# Display-RTC.net
KiCad netlist of a schematic drawn in Altium Designer
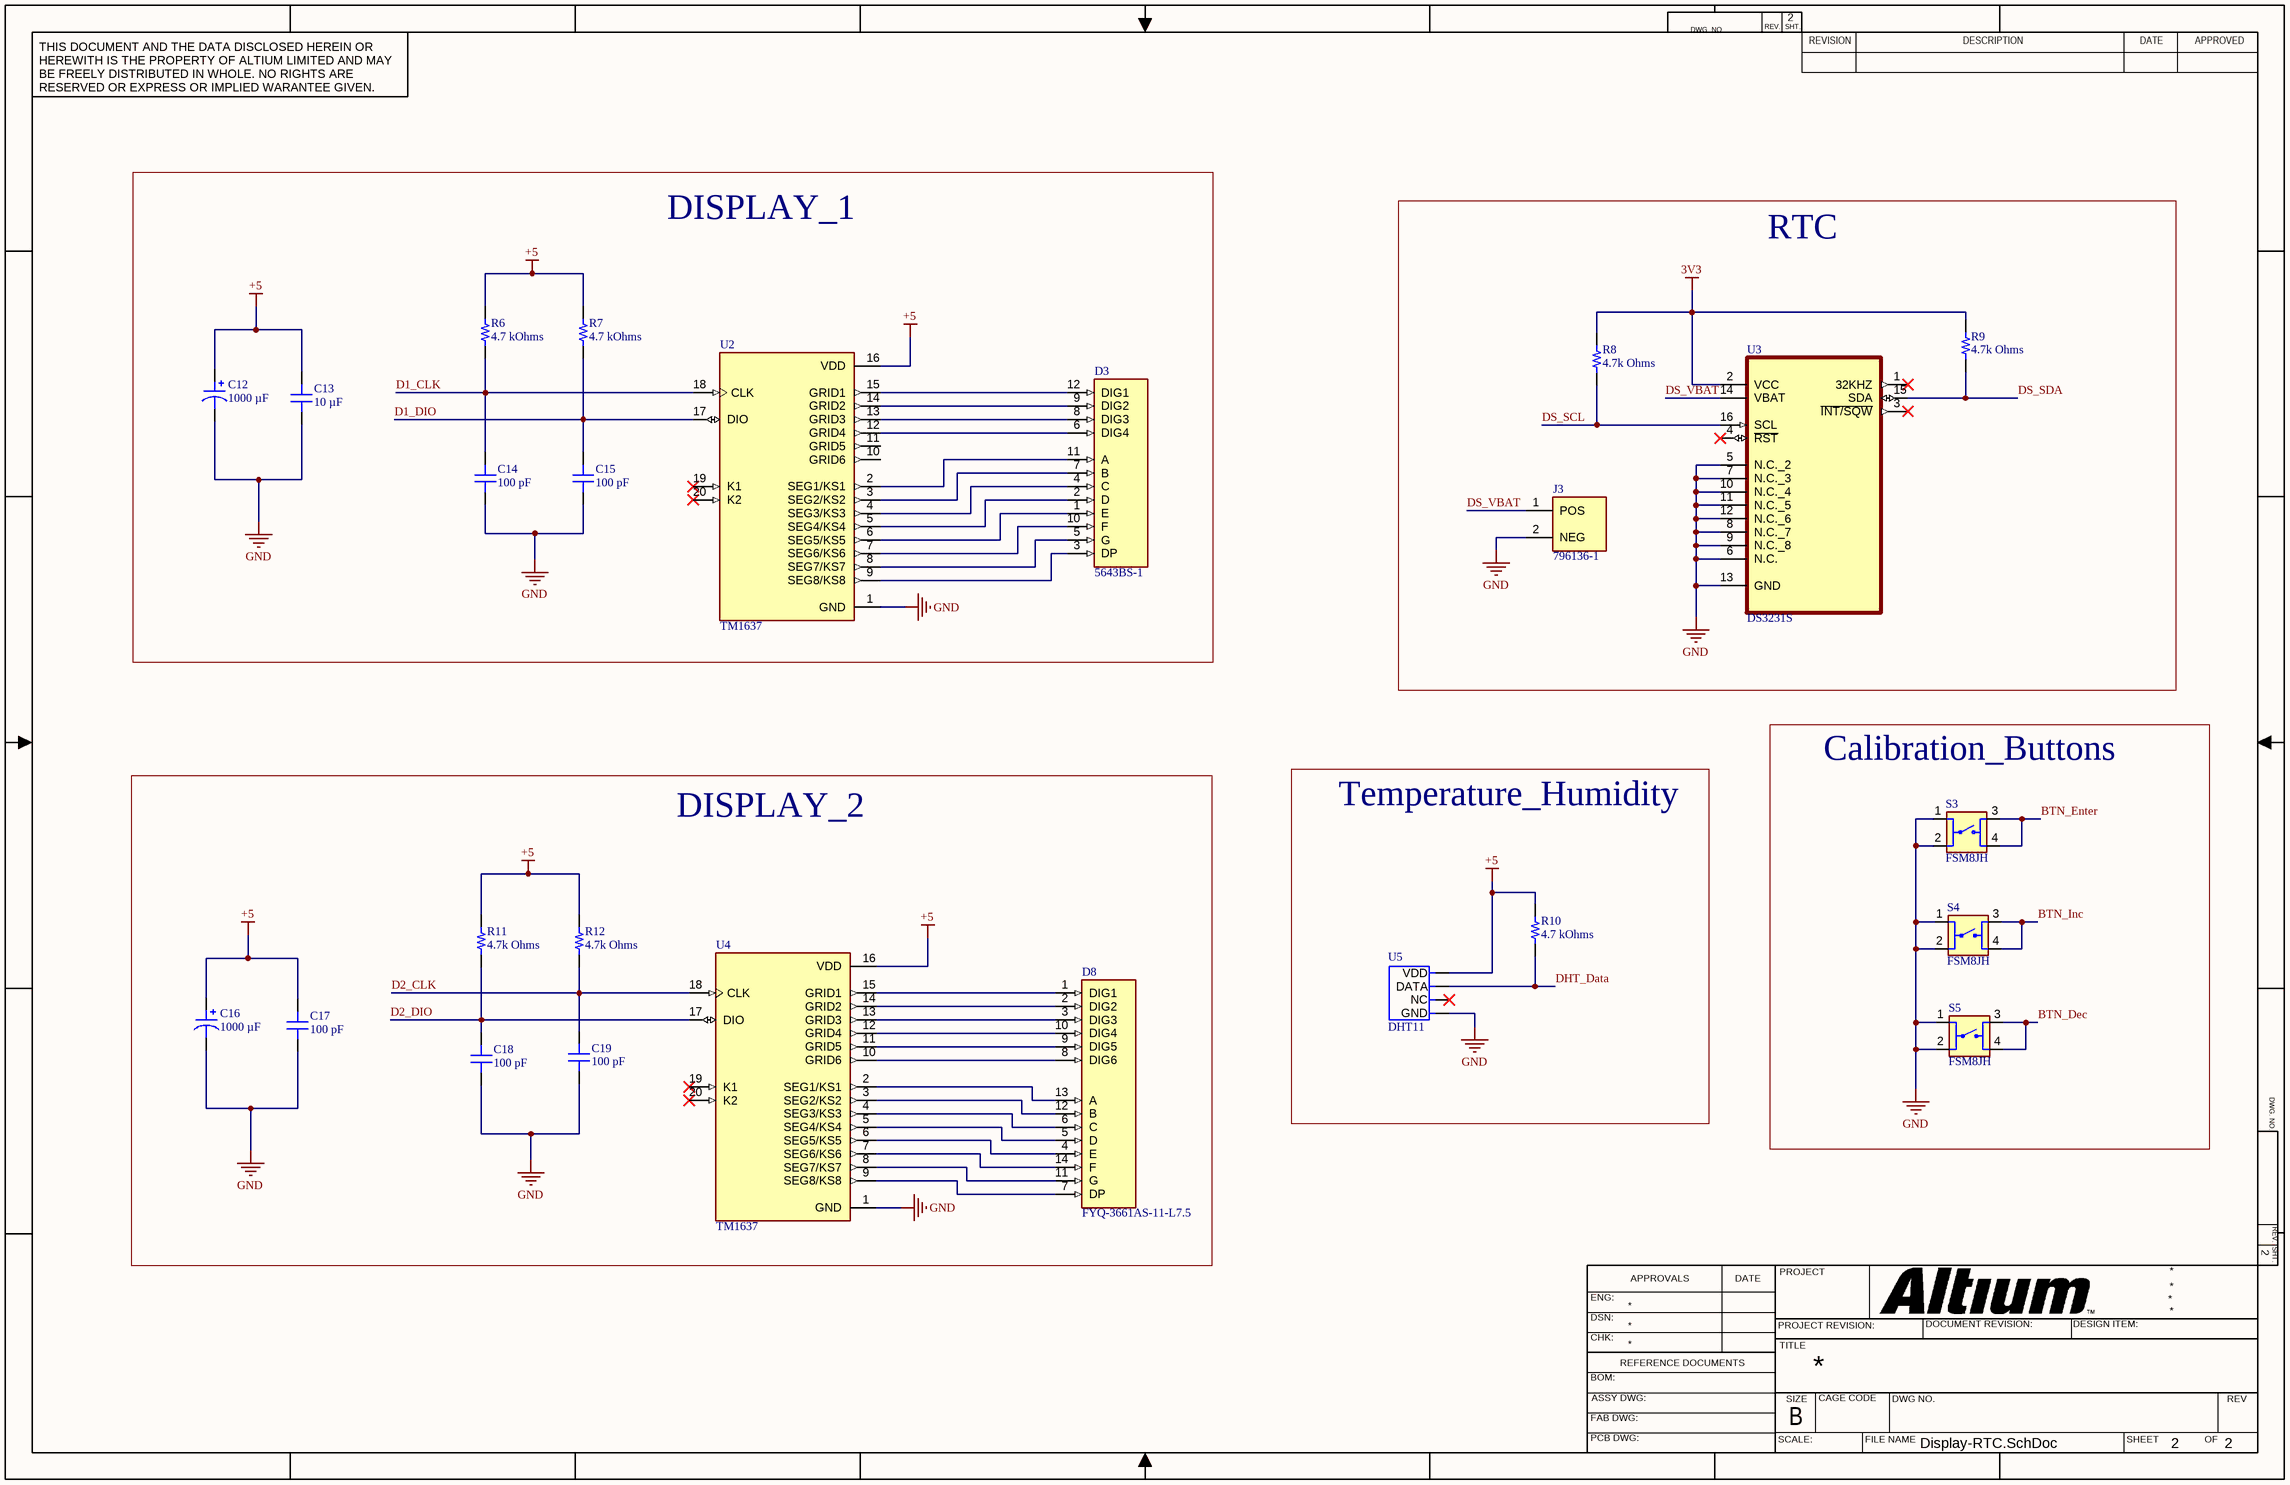
[diagram p0: Display-RTC.SchDoc]

(export (version "E")
  (design (tool "Eeschema 10.0.6"))
  (components
    (comp (ref "C12")
      (value "1000 µF")
      (footprint "CAP AL TH D8 L3.5 H12.5")
      (description "CAP ALUM 1000UF 20% 6.3V RADIAL")
      (fields
        (field (name "PART NUMBER") "ECA-0JHG102")
        (field (name "MANUFACTURER") "Panasonic Electronic Components")
      )
      (libsource (lib "Celestial Altium Library - altium_library") (part "Polarised Capacitor"))
    )
    (comp (ref "C13")
      (value "10 µF")
      (footprint "CAP 0402_1005")
      (description "CAP CER 10UF 10V X5R 0402")
      (fields
        (field (name "PART NUMBER") "CL05A106MP8NUB8")
        (field (name "CAPACITANCE") "10 µF")
        (field (name "MANUFACTURER") "Samsung Electro-Mechanics")
      )
      (libsource (lib "Celestial Altium Library - altium_library") (part "Capacitor"))
    )
    (comp (ref "C14")
      (value "100 pF")
      (footprint "CAP 0402_1005")
      (description "CAP CER 100PF 50V C0G/NP0 0402")
      (fields
        (field (name "PART NUMBER") "500X07N101MV4T")
        (field (name "CAPACITANCE") "100 pF")
        (field (name "MANUFACTURER") "Johanson Dielectrics Inc.")
      )
      (libsource (lib "Celestial Altium Library - altium_library") (part "Capacitor"))
    )
    (comp (ref "C15")
      (value "100 pF")
      (footprint "CAP 0402_1005")
      (description "CAP CER 100PF 50V C0G/NP0 0402")
      (fields
        (field (name "PART NUMBER") "500X07N101MV4T")
        (field (name "CAPACITANCE") "100 pF")
        (field (name "MANUFACTURER") "Johanson Dielectrics Inc.")
      )
      (libsource (lib "Celestial Altium Library - altium_library") (part "Capacitor"))
    )
    (comp (ref "C16")
      (value "1000 µF")
      (footprint "CAP AL TH D8 L3.5 H12.5")
      (description "CAP ALUM 1000UF 20% 6.3V RADIAL")
      (fields
        (field (name "PART NUMBER") "ECA-0JHG102")
        (field (name "MANUFACTURER") "Panasonic Electronic Components")
      )
      (libsource (lib "Celestial Altium Library - altium_library") (part "Polarised Capacitor"))
    )
    (comp (ref "C17")
      (value "100 pF")
      (footprint "CAP 0402_1005")
      (description "CAP CER 100PF 50V C0G/NP0 0402")
      (fields
        (field (name "PART NUMBER") "500X07N101MV4T")
        (field (name "CAPACITANCE") "100 pF")
        (field (name "MANUFACTURER") "Johanson Dielectrics Inc.")
      )
      (libsource (lib "Celestial Altium Library - altium_library") (part "Capacitor"))
    )
    (comp (ref "C18")
      (value "100 pF")
      (footprint "CAP 0402_1005")
      (description "CAP CER 100PF 50V C0G/NP0 0402")
      (fields
        (field (name "PART NUMBER") "500X07N101MV4T")
        (field (name "CAPACITANCE") "100 pF")
        (field (name "MANUFACTURER") "Johanson Dielectrics Inc.")
      )
      (libsource (lib "Celestial Altium Library - altium_library") (part "Capacitor"))
    )
    (comp (ref "C19")
      (value "100 pF")
      (footprint "CAP 0402_1005")
      (description "CAP CER 100PF 50V C0G/NP0 0402")
      (fields
        (field (name "PART NUMBER") "500X07N101MV4T")
        (field (name "CAPACITANCE") "100 pF")
        (field (name "MANUFACTURER") "Johanson Dielectrics Inc.")
      )
      (libsource (lib "Celestial Altium Library - altium_library") (part "Capacitor"))
    )
    (comp (ref "D3") (value "5643BS-1") (footprint "5643BS-1") (libsource (lib "MyAltLib") (part "5643BS-1")))
    (comp (ref "D8")
      (value "FYQ-3661AS-11-L7.5")
      (footprint "FYQ-3661AS-11-L7.5")
      (libsource (lib "MyAltLib") (part "FYQ-3661AS-11-L7.5"))
    )
    (comp (ref "J3")
      (value "796136-1")
      (footprint "TE_796136-1")
      (description "BATTERY HOLDER COIN 20MM SMD")
      (libsource (lib "MyAltLib") (part "796136-1"))
    )
    (comp (ref "R6")
      (value "4.7 kOhms")
      (footprint "RES 0805_2012")
      (description "CRGH0805 1% 4K7 0.33W")
      (fields
        (field (name "PART NUMBER") "CRGH0805F4K7")
        (field (name "MANUFACTURER") "TE Connectivity Passive Product")
      )
      (libsource (lib "Celestial Altium Library - altium_library") (part "Resistor"))
    )
    (comp (ref "R7")
      (value "4.7 kOhms")
      (footprint "RES 0805_2012")
      (description "CRGH0805 1% 4K7 0.33W")
      (fields
        (field (name "PART NUMBER") "CRGH0805F4K7")
        (field (name "MANUFACTURER") "TE Connectivity Passive Product")
      )
      (libsource (lib "Celestial Altium Library - altium_library") (part "Resistor"))
    )
    (comp (ref "R8")
      (value "4.7k Ohms")
      (footprint "RES 0805_2012")
      (description "RES 0 OHM JUMPER 0805")
      (fields
        (field (name "PART NUMBER") "TLRZ2ATTD")
        (field (name "MANUFACTURER") "KOA Speer Electronics, Inc.")
      )
      (libsource (lib "Celestial Altium Library - altium_library") (part "Resistor"))
    )
    (comp (ref "R9")
      (value "4.7k Ohms")
      (footprint "RES 0805_2012")
      (description "RES 0 OHM JUMPER 0805")
      (fields
        (field (name "PART NUMBER") "TLRZ2ATTD")
        (field (name "MANUFACTURER") "KOA Speer Electronics, Inc.")
      )
      (libsource (lib "Celestial Altium Library - altium_library") (part "Resistor"))
    )
    (comp (ref "R10")
      (value "4.7 kOhms")
      (footprint "RES 0805_2012")
      (description "CRGH0805 1% 4K7 0.33W")
      (fields
        (field (name "PART NUMBER") "CRGH0805F4K7")
        (field (name "MANUFACTURER") "TE Connectivity Passive Product")
      )
      (libsource (lib "Celestial Altium Library - altium_library") (part "Resistor"))
    )
    (comp (ref "R11")
      (value "4.7k Ohms")
      (footprint "RES 0805_2012")
      (description "RES 0 OHM JUMPER 0805")
      (fields
        (field (name "PART NUMBER") "TLRZ2ATTD")
        (field (name "MANUFACTURER") "KOA Speer Electronics, Inc.")
      )
      (libsource (lib "Celestial Altium Library - altium_library") (part "Resistor"))
    )
    (comp (ref "R12")
      (value "4.7k Ohms")
      (footprint "RES 0805_2012")
      (description "RES 0 OHM JUMPER 0805")
      (fields
        (field (name "PART NUMBER") "TLRZ2ATTD")
        (field (name "MANUFACTURER") "KOA Speer Electronics, Inc.")
      )
      (libsource (lib "Celestial Altium Library - altium_library") (part "Resistor"))
    )
    (comp (ref "S3")
      (value "FSM8JH")
      (footprint "SW_FSM8JH")
      (description "Tactile Switch SPST-NO Top Actuated Through Hole")
      (fields (field (name "MF") "TE Connectivity"))
      (libsource (lib "MyAltLib") (part "FSM8JH"))
    )
    (comp (ref "S4")
      (value "FSM8JH")
      (footprint "SW_FSM8JH")
      (description "Tactile Switch SPST-NO Top Actuated Through Hole")
      (fields (field (name "MF") "TE Connectivity"))
      (libsource (lib "MyAltLib") (part "FSM8JH"))
    )
    (comp (ref "S5")
      (value "FSM8JH")
      (footprint "SW_FSM8JH")
      (description "Tactile Switch SPST-NO Top Actuated Through Hole")
      (fields (field (name "MF") "TE Connectivity"))
      (libsource (lib "MyAltLib") (part "FSM8JH"))
    )
    (comp (ref "U2")
      (value "TM1637")
      (footprint "TM1637")
      (description "LED Drive Control Special Circuit")
      (fields (field (name "MF") "Titan Micro Electronics"))
      (libsource (lib "MyAltLib") (part "TM1637"))
    )
    (comp (ref "U3")
      (value "DS3231S")
      (footprint "SOIC16")
      (description "Real Time Clock (RTC) IC Clock/Calendar - IÂ²C, 2-Wire Serial 16-SOIC (0.295, 7.50mm Width)")
      (fields (field (name "MF") "Maxim Integrated") (field (name "MP") "DS3231S#"))
      (libsource (lib "MyAltLib") (part "DS3231S"))
    )
    (comp (ref "U4")
      (value "TM1637")
      (footprint "TM1637")
      (description "LED Drive Control Special Circuit")
      (fields (field (name "MF") "Titan Micro Electronics"))
      (libsource (lib "MyAltLib") (part "TM1637"))
    )
    (comp (ref "U5")
      (value "DHT11")
      (footprint "DHT11")
      (description "Servo AC 100 ~ 120VAC Supply 10A 120V Load")
      (fields (field (name "MF") "Panasonic Industrial Automation Sales"))
      (libsource (lib "MyAltLib") (part "DHT11"))
    )
  )
  (nets
    (net (code "1") (name "+5") (class "Default")
      (node (ref "C12") (pin "1") (pinfunction "1_1") (pintype "passive"))
      (node (ref "C13") (pin "2") (pinfunction "2_2") (pintype "passive"))
      (node (ref "C16") (pin "1") (pinfunction "1_1") (pintype "passive"))
      (node (ref "C17") (pin "2") (pinfunction "2_2") (pintype "passive"))
      (node (ref "R10") (pin "2") (pinfunction "2_2") (pintype "passive"))
      (node (ref "R11") (pin "2") (pinfunction "2_2") (pintype "passive"))
      (node (ref "R12") (pin "2") (pinfunction "2_2") (pintype "passive"))
      (node (ref "R6") (pin "2") (pinfunction "2_2") (pintype "passive"))
      (node (ref "R7") (pin "2") (pinfunction "2_2") (pintype "passive"))
      (node (ref "U2") (pin "16") (pinfunction "VDD_16") (pintype "power_in"))
      (node (ref "U4") (pin "16") (pinfunction "VDD_16") (pintype "power_in"))
      (node (ref "U5") (pin "1") (pinfunction "VDD_1") (pintype "power_in"))
    )
    (net (code "2") (name "/BTN_Dec") (class "Default")
      (node (ref "S5") (pin "3") (pinfunction "3_3") (pintype "passive"))
      (node (ref "S5") (pin "4") (pinfunction "4_4") (pintype "passive"))
    )
    (net (code "3") (name "/BTN_Enter") (class "Default")
      (node (ref "S3") (pin "3") (pinfunction "3_3") (pintype "passive"))
      (node (ref "S3") (pin "4") (pinfunction "4_4") (pintype "passive"))
    )
    (net (code "4") (name "/BTN_Inc") (class "Default")
      (node (ref "S4") (pin "3") (pinfunction "3_3") (pintype "passive"))
      (node (ref "S4") (pin "4") (pinfunction "4_4") (pintype "passive"))
    )
    (net (code "5") (name "/D1_CLK") (class "Default")
      (node (ref "C14") (pin "2") (pinfunction "2_2") (pintype "passive"))
      (node (ref "R6") (pin "1") (pinfunction "1_1") (pintype "passive"))
      (node (ref "U2") (pin "18") (pinfunction "CLK_18") (pintype "input"))
    )
    (net (code "6") (name "/D1_DIO") (class "Default")
      (node (ref "C15") (pin "2") (pinfunction "2_2") (pintype "passive"))
      (node (ref "R7") (pin "1") (pinfunction "1_1") (pintype "passive"))
      (node (ref "U2") (pin "17") (pinfunction "DIO_17") (pintype "bidirectional"))
    )
    (net (code "7") (name "/D2_CLK") (class "Default")
      (node (ref "C19") (pin "2") (pinfunction "2_2") (pintype "passive"))
      (node (ref "R12") (pin "1") (pinfunction "1_1") (pintype "passive"))
      (node (ref "U4") (pin "18") (pinfunction "CLK_18") (pintype "input"))
    )
    (net (code "8") (name "/D2_DIO") (class "Default")
      (node (ref "C18") (pin "2") (pinfunction "2_2") (pintype "passive"))
      (node (ref "R11") (pin "1") (pinfunction "1_1") (pintype "passive"))
      (node (ref "U4") (pin "17") (pinfunction "DIO_17") (pintype "bidirectional"))
    )
    (net (code "9") (name "/DHT_Data") (class "Default")
      (node (ref "R10") (pin "1") (pinfunction "1_1") (pintype "passive"))
      (node (ref "U5") (pin "2") (pinfunction "DATA_2") (pintype "bidirectional"))
    )
    (net (code "10") (name "/DS_SCL") (class "Default")
      (node (ref "R8") (pin "1") (pinfunction "1_1") (pintype "passive"))
      (node (ref "U3") (pin "16") (pinfunction "SCL_16") (pintype "input"))
    )
    (net (code "11") (name "/DS_SDA") (class "Default")
      (node (ref "R9") (pin "1") (pinfunction "1_1") (pintype "passive"))
      (node (ref "U3") (pin "15") (pinfunction "SDA_15") (pintype "bidirectional"))
    )
    (net (code "12") (name "/DS_VBAT") (class "Default")
      (node (ref "J3") (pin "1") (pinfunction "POS_1") (pintype "passive"))
      (node (ref "U3") (pin "14") (pinfunction "VBAT_14") (pintype "power_in"))
    )
    (net (code "13") (name "3V3") (class "Default")
      (node (ref "R8") (pin "2") (pinfunction "2_2") (pintype "passive"))
      (node (ref "R9") (pin "2") (pinfunction "2_2") (pintype "passive"))
      (node (ref "U3") (pin "2") (pinfunction "VCC_2") (pintype "power_in"))
    )
    (net (code "14") (name "GND") (class "Default")
      (node (ref "C12") (pin "2") (pinfunction "2_2") (pintype "passive"))
      (node (ref "C13") (pin "1") (pinfunction "1_1") (pintype "passive"))
      (node (ref "C14") (pin "1") (pinfunction "1_1") (pintype "passive"))
      (node (ref "C15") (pin "1") (pinfunction "1_1") (pintype "passive"))
      (node (ref "C16") (pin "2") (pinfunction "2_2") (pintype "passive"))
      (node (ref "C17") (pin "1") (pinfunction "1_1") (pintype "passive"))
      (node (ref "C18") (pin "1") (pinfunction "1_1") (pintype "passive"))
      (node (ref "C19") (pin "1") (pinfunction "1_1") (pintype "passive"))
      (node (ref "J3") (pin "2") (pinfunction "NEG_2") (pintype "passive"))
      (node (ref "S3") (pin "1") (pinfunction "1_1") (pintype "passive"))
      (node (ref "S3") (pin "2") (pinfunction "2_2") (pintype "passive"))
      (node (ref "S4") (pin "1") (pinfunction "1_1") (pintype "passive"))
      (node (ref "S4") (pin "2") (pinfunction "2_2") (pintype "passive"))
      (node (ref "S5") (pin "1") (pinfunction "1_1") (pintype "passive"))
      (node (ref "S5") (pin "2") (pinfunction "2_2") (pintype "passive"))
      (node (ref "U2") (pin "1") (pinfunction "GND_1") (pintype "power_in"))
      (node (ref "U3") (pin "10") (pinfunction "N.C._4_10") (pintype "passive"))
      (node (ref "U3") (pin "11") (pinfunction "N.C._5_11") (pintype "passive"))
      (node (ref "U3") (pin "12") (pinfunction "N.C._6_12") (pintype "passive"))
      (node (ref "U3") (pin "13") (pinfunction "GND_13") (pintype "passive"))
      (node (ref "U3") (pin "5") (pinfunction "N.C._2_5") (pintype "passive"))
      (node (ref "U3") (pin "6") (pinfunction "N.C._6") (pintype "passive"))
      (node (ref "U3") (pin "7") (pinfunction "N.C._3_7") (pintype "passive"))
      (node (ref "U3") (pin "8") (pinfunction "N.C._7_8") (pintype "passive"))
      (node (ref "U3") (pin "9") (pinfunction "N.C._8_9") (pintype "passive"))
      (node (ref "U4") (pin "1") (pinfunction "GND_1") (pintype "power_in"))
      (node (ref "U5") (pin "4") (pinfunction "GND_4") (pintype "power_in"))
    )
    (net (code "15") (name "Net-(D3-A)") (class "Default")
      (node (ref "D3") (pin "11") (pinfunction "A_11") (pintype "input"))
      (node (ref "U2") (pin "2") (pinfunction "SEG1/KS1_2") (pintype "output"))
    )
    (net (code "16") (name "Net-(D3-B)") (class "Default")
      (node (ref "D3") (pin "7") (pinfunction "B_7") (pintype "input"))
      (node (ref "U2") (pin "3") (pinfunction "SEG2/KS2_3") (pintype "output"))
    )
    (net (code "17") (name "Net-(D3-C)") (class "Default")
      (node (ref "D3") (pin "4") (pinfunction "C_4") (pintype "input"))
      (node (ref "U2") (pin "4") (pinfunction "SEG3/KS3_4") (pintype "output"))
    )
    (net (code "18") (name "Net-(D3-D)") (class "Default")
      (node (ref "D3") (pin "2") (pinfunction "D_2") (pintype "input"))
      (node (ref "U2") (pin "5") (pinfunction "SEG4/KS4_5") (pintype "output"))
    )
    (net (code "19") (name "Net-(D3-DIG1)") (class "Default")
      (node (ref "D3") (pin "12") (pinfunction "DIG1_12") (pintype "input"))
      (node (ref "U2") (pin "15") (pinfunction "GRID1_15") (pintype "output"))
    )
    (net (code "20") (name "Net-(D3-DIG2)") (class "Default")
      (node (ref "D3") (pin "9") (pinfunction "DIG2_9") (pintype "input"))
      (node (ref "U2") (pin "14") (pinfunction "GRID2_14") (pintype "output"))
    )
    (net (code "21") (name "Net-(D3-DIG3)") (class "Default")
      (node (ref "D3") (pin "8") (pinfunction "DIG3_8") (pintype "input"))
      (node (ref "U2") (pin "13") (pinfunction "GRID3_13") (pintype "output"))
    )
    (net (code "22") (name "Net-(D3-DIG4)") (class "Default")
      (node (ref "D3") (pin "6") (pinfunction "DIG4_6") (pintype "input"))
      (node (ref "U2") (pin "12") (pinfunction "GRID4_12") (pintype "output"))
    )
    (net (code "23") (name "Net-(D3-DP)") (class "Default")
      (node (ref "D3") (pin "3") (pinfunction "DP_3") (pintype "input"))
      (node (ref "U2") (pin "9") (pinfunction "SEG8/KS8_9") (pintype "output"))
    )
    (net (code "24") (name "Net-(D3-E)") (class "Default")
      (node (ref "D3") (pin "1") (pinfunction "E_1") (pintype "input"))
      (node (ref "U2") (pin "6") (pinfunction "SEG5/KS5_6") (pintype "output"))
    )
    (net (code "25") (name "Net-(D3-F)") (class "Default")
      (node (ref "D3") (pin "10") (pinfunction "F_10") (pintype "input"))
      (node (ref "U2") (pin "7") (pinfunction "SEG6/KS6_7") (pintype "output"))
    )
    (net (code "26") (name "Net-(D3-G)") (class "Default")
      (node (ref "D3") (pin "5") (pinfunction "G_5") (pintype "input"))
      (node (ref "U2") (pin "8") (pinfunction "SEG7/KS7_8") (pintype "output"))
    )
    (net (code "27") (name "Net-(D8-A)") (class "Default")
      (node (ref "D8") (pin "13") (pinfunction "A_13") (pintype "input"))
      (node (ref "U4") (pin "2") (pinfunction "SEG1/KS1_2") (pintype "output"))
    )
    (net (code "28") (name "Net-(D8-B)") (class "Default")
      (node (ref "D8") (pin "12") (pinfunction "B_12") (pintype "input"))
      (node (ref "U4") (pin "3") (pinfunction "SEG2/KS2_3") (pintype "output"))
    )
    (net (code "29") (name "Net-(D8-C)") (class "Default")
      (node (ref "D8") (pin "6") (pinfunction "C_6") (pintype "input"))
      (node (ref "U4") (pin "4") (pinfunction "SEG3/KS3_4") (pintype "output"))
    )
    (net (code "30") (name "Net-(D8-D)") (class "Default")
      (node (ref "D8") (pin "5") (pinfunction "D_5") (pintype "input"))
      (node (ref "U4") (pin "5") (pinfunction "SEG4/KS4_5") (pintype "output"))
    )
    (net (code "31") (name "Net-(D8-DIG1)") (class "Default")
      (node (ref "D8") (pin "1") (pinfunction "DIG1_1") (pintype "input"))
      (node (ref "U4") (pin "15") (pinfunction "GRID1_15") (pintype "output"))
    )
    (net (code "32") (name "Net-(D8-DIG2)") (class "Default")
      (node (ref "D8") (pin "2") (pinfunction "DIG2_2") (pintype "input"))
      (node (ref "U4") (pin "14") (pinfunction "GRID2_14") (pintype "output"))
    )
    (net (code "33") (name "Net-(D8-DIG3)") (class "Default")
      (node (ref "D8") (pin "3") (pinfunction "DIG3_3") (pintype "input"))
      (node (ref "U4") (pin "13") (pinfunction "GRID3_13") (pintype "output"))
    )
    (net (code "34") (name "Net-(D8-DIG4)") (class "Default")
      (node (ref "D8") (pin "10") (pinfunction "DIG4_10") (pintype "input"))
      (node (ref "U4") (pin "12") (pinfunction "GRID4_12") (pintype "output"))
    )
    (net (code "35") (name "Net-(D8-DIG5)") (class "Default")
      (node (ref "D8") (pin "9") (pinfunction "DIG5_9") (pintype "input"))
      (node (ref "U4") (pin "11") (pinfunction "GRID5_11") (pintype "output"))
    )
    (net (code "36") (name "Net-(D8-DIG6)") (class "Default")
      (node (ref "D8") (pin "8") (pinfunction "DIG6_8") (pintype "input"))
      (node (ref "U4") (pin "10") (pinfunction "GRID6_10") (pintype "output"))
    )
    (net (code "37") (name "Net-(D8-DP)") (class "Default")
      (node (ref "D8") (pin "7") (pinfunction "DP_7") (pintype "input"))
      (node (ref "U4") (pin "9") (pinfunction "SEG8/KS8_9") (pintype "output"))
    )
    (net (code "38") (name "Net-(D8-E)") (class "Default")
      (node (ref "D8") (pin "4") (pinfunction "E_4") (pintype "input"))
      (node (ref "U4") (pin "6") (pinfunction "SEG5/KS5_6") (pintype "output"))
    )
    (net (code "39") (name "Net-(D8-F)") (class "Default")
      (node (ref "D8") (pin "14") (pinfunction "F_14") (pintype "input"))
      (node (ref "U4") (pin "7") (pinfunction "SEG6/KS6_7") (pintype "output"))
    )
    (net (code "40") (name "Net-(D8-G)") (class "Default")
      (node (ref "D8") (pin "11") (pinfunction "G_11") (pintype "input"))
      (node (ref "U4") (pin "8") (pinfunction "SEG7/KS7_8") (pintype "output"))
    )
    (net (code "41") (name "unconnected-(U2-GRID5-Pad11)") (class "Default")
      (node (ref "U2") (pin "11") (pinfunction "GRID5_11") (pintype "output"))
    )
    (net (code "42") (name "unconnected-(U2-GRID6-Pad10)") (class "Default")
      (node (ref "U2") (pin "10") (pinfunction "GRID6_10") (pintype "output"))
    )
    (net (code "43") (name "unconnected-(U2-K1-Pad19)") (class "Default")
      (node (ref "U2") (pin "19") (pinfunction "K1_19") (pintype "input+no_connect"))
    )
    (net (code "44") (name "unconnected-(U2-K2-Pad20)") (class "Default")
      (node (ref "U2") (pin "20") (pinfunction "K2_20") (pintype "input+no_connect"))
    )
    (net (code "45") (name "unconnected-(U3-32KHZ-Pad1)") (class "Default")
      (node (ref "U3") (pin "1") (pinfunction "32KHZ_1") (pintype "output+no_connect"))
    )
    (net (code "46") (name "unconnected-(U3-~{INT{slash}SQW}-Pad3)") (class "Default")
      (node (ref "U3") (pin "3") (pinfunction "~{INT/SQW}_3") (pintype "output+no_connect"))
    )
    (net (code "47") (name "unconnected-(U3-~{RST}-Pad4)") (class "Default")
      (node (ref "U3") (pin "4") (pinfunction "~{RST}_4") (pintype "bidirectional+no_connect"))
    )
    (net (code "48") (name "unconnected-(U4-K1-Pad19)") (class "Default")
      (node (ref "U4") (pin "19") (pinfunction "K1_19") (pintype "input+no_connect"))
    )
    (net (code "49") (name "unconnected-(U4-K2-Pad20)") (class "Default")
      (node (ref "U4") (pin "20") (pinfunction "K2_20") (pintype "input+no_connect"))
    )
    (net (code "50") (name "unconnected-(U5-NC-Pad3)") (class "Default")
      (node (ref "U5") (pin "3") (pinfunction "NC_3") (pintype "passive+no_connect"))
    )
  )
)
